# MRCS-Telephone-Connector-V2_1.net
KiCad netlist of a schematic drawn in EAGLE
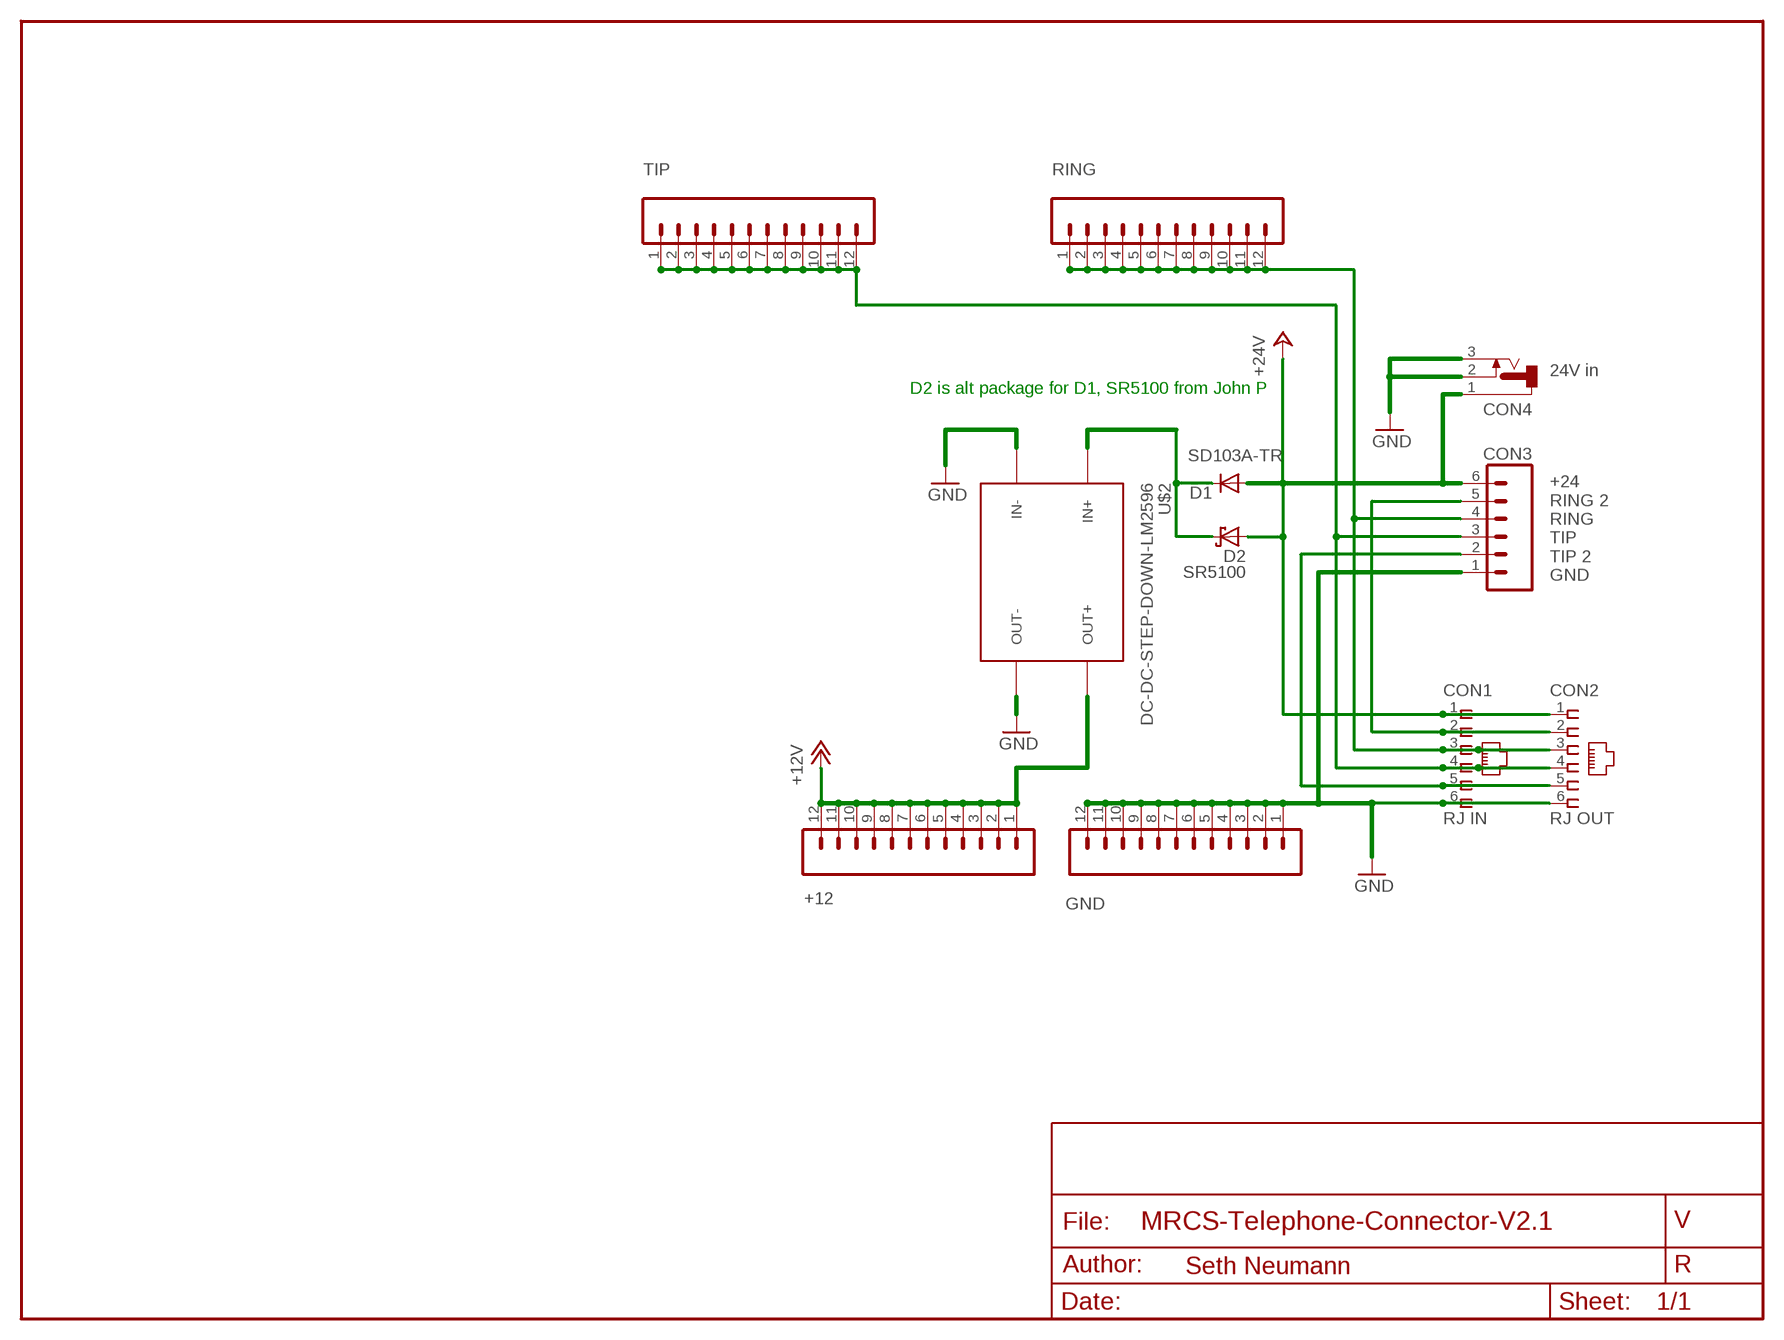
[diagram p0: schematic, sheet 1]

(export (version "E")
  (design (tool "Eeschema 10.0.6"))
  (components
    (comp (ref "+12")
      (value "CONNECTOR-M12LOCK")
      (footprint "eagle-import:1X12_LOCK")
      (libsource (lib "eagle-import") (part "CONNECTOR-M12LOCK"))
    )
    (comp (ref "CON1")
      (value "RJ IN")
      (footprint "eagle-import:RJ25-INVERTED")
      (libsource (lib "eagle-import") (part "CONNECTOR-RJ25-43860-2-MOLEX"))
    )
    (comp (ref "CON2")
      (value "RJ OUT")
      (footprint "eagle-import:RJ25-INVERTED")
      (libsource (lib "eagle-import") (part "CONNECTOR-RJ25-43860-2-MOLEX"))
    )
    (comp (ref "CON3")
      (value "CONNECTOR-M06LOCK")
      (footprint "eagle-import:1X06_LOCK")
      (libsource (lib "eagle-import") (part "CONNECTOR-M06LOCK"))
    )
    (comp (ref "CON4")
      (value "CONNECTOR-DC-POWER-RA")
      (footprint "eagle-import:DCJ0202")
      (libsource (lib "eagle-import") (part "CONNECTOR-DC-POWER-RA"))
    )
    (comp (ref "D1")
      (value "SD103A-TR")
      (footprint "eagle-import:DIODE-1N4001")
      (libsource (lib "eagle-import") (part "DIODEPTH"))
    )
    (comp (ref "D2")
      (value "SR5100")
      (footprint "eagle-import:AG")
      (libsource (lib "eagle-import") (part "SCHOTTKY-DIODEAG"))
    )
    (comp (ref "GND")
      (value "CONNECTOR-M12LOCK")
      (footprint "eagle-import:1X12_LOCK")
      (libsource (lib "eagle-import") (part "CONNECTOR-M12LOCK"))
    )
    (comp (ref "RING")
      (value "CONNECTOR-M12LOCK")
      (footprint "eagle-import:1X12_LOCK")
      (libsource (lib "eagle-import") (part "CONNECTOR-M12LOCK"))
    )
    (comp (ref "TIP")
      (value "CONNECTOR-M12LOCK")
      (footprint "eagle-import:1X12_LOCK")
      (libsource (lib "eagle-import") (part "CONNECTOR-M12LOCK"))
    )
    (comp (ref "U$2")
      (value "DC-DC-STEP-DOWN-LM2596")
      (footprint "eagle-import:DC-DC-STEP-DOWN-LM2596")
      (libsource (lib "eagle-import") (part "DC-DC-STEP-DOWN-LM2596"))
    )
  )
  (nets
    (net (code "1") (name "+12V") (class "Default")
      (node (ref "+12") (pin "1") (pinfunction "1_1") (pintype "passive"))
      (node (ref "+12") (pin "10") (pinfunction "10_10") (pintype "passive"))
      (node (ref "+12") (pin "11") (pinfunction "11_11") (pintype "passive"))
      (node (ref "+12") (pin "12") (pinfunction "12_12") (pintype "passive"))
      (node (ref "+12") (pin "2") (pinfunction "2_2") (pintype "passive"))
      (node (ref "+12") (pin "3") (pinfunction "3_3") (pintype "passive"))
      (node (ref "+12") (pin "4") (pinfunction "4_4") (pintype "passive"))
      (node (ref "+12") (pin "5") (pinfunction "5_5") (pintype "passive"))
      (node (ref "+12") (pin "6") (pinfunction "6_6") (pintype "passive"))
      (node (ref "+12") (pin "7") (pinfunction "7_7") (pintype "passive"))
      (node (ref "+12") (pin "8") (pinfunction "8_8") (pintype "passive"))
      (node (ref "+12") (pin "9") (pinfunction "9_9") (pintype "passive"))
      (node (ref "U$2") (pin "OUT+") (pinfunction "OUT+_OUT+") (pintype "bidirectional"))
    )
    (net (code "2") (name "+24V") (class "Default")
      (node (ref "CON1") (pin "1") (pinfunction "1_1") (pintype "passive"))
      (node (ref "CON2") (pin "1") (pinfunction "1_1") (pintype "passive"))
      (node (ref "CON3") (pin "6") (pinfunction "6_6") (pintype "passive"))
      (node (ref "CON4") (pin "1") (pinfunction "1_1") (pintype "passive"))
      (node (ref "D1") (pin "A") (pinfunction "A_A") (pintype "passive"))
      (node (ref "D2") (pin "A") (pinfunction "A_A") (pintype "passive"))
    )
    (net (code "3") (name "GND") (class "Default")
      (node (ref "CON1") (pin "6") (pinfunction "6_6") (pintype "passive"))
      (node (ref "CON2") (pin "6") (pinfunction "6_6") (pintype "passive"))
      (node (ref "CON3") (pin "1") (pinfunction "1_1") (pintype "passive"))
      (node (ref "CON4") (pin "2") (pinfunction "2_2") (pintype "passive"))
      (node (ref "CON4") (pin "3") (pinfunction "3_3") (pintype "passive"))
      (node (ref "GND") (pin "1") (pinfunction "1_1") (pintype "passive"))
      (node (ref "GND") (pin "10") (pinfunction "10_10") (pintype "passive"))
      (node (ref "GND") (pin "11") (pinfunction "11_11") (pintype "passive"))
      (node (ref "GND") (pin "12") (pinfunction "12_12") (pintype "passive"))
      (node (ref "GND") (pin "2") (pinfunction "2_2") (pintype "passive"))
      (node (ref "GND") (pin "3") (pinfunction "3_3") (pintype "passive"))
      (node (ref "GND") (pin "4") (pinfunction "4_4") (pintype "passive"))
      (node (ref "GND") (pin "5") (pinfunction "5_5") (pintype "passive"))
      (node (ref "GND") (pin "6") (pinfunction "6_6") (pintype "passive"))
      (node (ref "GND") (pin "7") (pinfunction "7_7") (pintype "passive"))
      (node (ref "GND") (pin "8") (pinfunction "8_8") (pintype "passive"))
      (node (ref "GND") (pin "9") (pinfunction "9_9") (pintype "passive"))
      (node (ref "U$2") (pin "IN-") (pinfunction "IN-_IN-") (pintype "bidirectional"))
      (node (ref "U$2") (pin "OUT-") (pinfunction "OUT-_OUT-") (pintype "bidirectional"))
    )
    (net (code "4") (name "Net-(CON1-Pad2)") (class "Default")
      (node (ref "CON1") (pin "2") (pinfunction "2_2") (pintype "passive"))
      (node (ref "CON2") (pin "2") (pinfunction "2_2") (pintype "passive"))
      (node (ref "CON3") (pin "5") (pinfunction "5_5") (pintype "passive"))
    )
    (net (code "5") (name "Net-(CON1-Pad3)") (class "Default")
      (node (ref "CON1") (pin "3") (pinfunction "3_3") (pintype "passive"))
      (node (ref "CON2") (pin "3") (pinfunction "3_3") (pintype "passive"))
      (node (ref "CON3") (pin "4") (pinfunction "4_4") (pintype "passive"))
      (node (ref "RING") (pin "1") (pinfunction "1_1") (pintype "passive"))
      (node (ref "RING") (pin "10") (pinfunction "10_10") (pintype "passive"))
      (node (ref "RING") (pin "11") (pinfunction "11_11") (pintype "passive"))
      (node (ref "RING") (pin "12") (pinfunction "12_12") (pintype "passive"))
      (node (ref "RING") (pin "2") (pinfunction "2_2") (pintype "passive"))
      (node (ref "RING") (pin "3") (pinfunction "3_3") (pintype "passive"))
      (node (ref "RING") (pin "4") (pinfunction "4_4") (pintype "passive"))
      (node (ref "RING") (pin "5") (pinfunction "5_5") (pintype "passive"))
      (node (ref "RING") (pin "6") (pinfunction "6_6") (pintype "passive"))
      (node (ref "RING") (pin "7") (pinfunction "7_7") (pintype "passive"))
      (node (ref "RING") (pin "8") (pinfunction "8_8") (pintype "passive"))
      (node (ref "RING") (pin "9") (pinfunction "9_9") (pintype "passive"))
    )
    (net (code "6") (name "Net-(CON1-Pad4)") (class "Default")
      (node (ref "CON1") (pin "4") (pinfunction "4_4") (pintype "passive"))
      (node (ref "CON2") (pin "4") (pinfunction "4_4") (pintype "passive"))
      (node (ref "CON3") (pin "3") (pinfunction "3_3") (pintype "passive"))
      (node (ref "TIP") (pin "1") (pinfunction "1_1") (pintype "passive"))
      (node (ref "TIP") (pin "10") (pinfunction "10_10") (pintype "passive"))
      (node (ref "TIP") (pin "11") (pinfunction "11_11") (pintype "passive"))
      (node (ref "TIP") (pin "12") (pinfunction "12_12") (pintype "passive"))
      (node (ref "TIP") (pin "2") (pinfunction "2_2") (pintype "passive"))
      (node (ref "TIP") (pin "3") (pinfunction "3_3") (pintype "passive"))
      (node (ref "TIP") (pin "4") (pinfunction "4_4") (pintype "passive"))
      (node (ref "TIP") (pin "5") (pinfunction "5_5") (pintype "passive"))
      (node (ref "TIP") (pin "6") (pinfunction "6_6") (pintype "passive"))
      (node (ref "TIP") (pin "7") (pinfunction "7_7") (pintype "passive"))
      (node (ref "TIP") (pin "8") (pinfunction "8_8") (pintype "passive"))
      (node (ref "TIP") (pin "9") (pinfunction "9_9") (pintype "passive"))
    )
    (net (code "7") (name "Net-(CON1-Pad5)") (class "Default")
      (node (ref "CON1") (pin "5") (pinfunction "5_5") (pintype "passive"))
      (node (ref "CON2") (pin "5") (pinfunction "5_5") (pintype "passive"))
      (node (ref "CON3") (pin "2") (pinfunction "2_2") (pintype "passive"))
    )
    (net (code "8") (name "Net-(D1-PadC)") (class "Default")
      (node (ref "D1") (pin "C") (pinfunction "C_C") (pintype "passive"))
      (node (ref "D2") (pin "C") (pinfunction "C_C") (pintype "passive"))
      (node (ref "U$2") (pin "IN+") (pinfunction "IN+_IN+") (pintype "bidirectional"))
    )
  )
)
